# design.net
KiCad netlist of a schematic drawn in Altium Designer
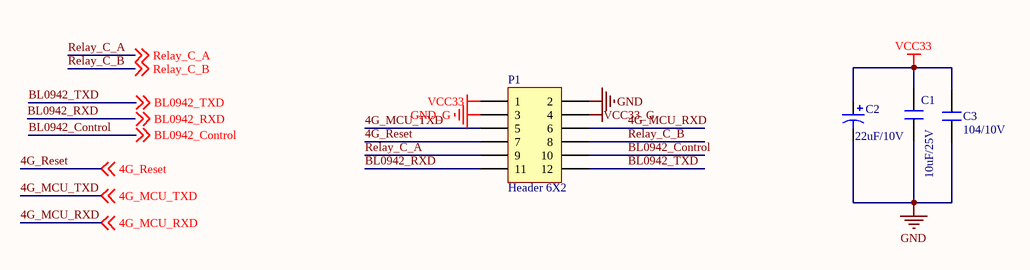
[diagram p0: 连接.SchDoc]

(export (version "E")
  (design (tool "Eeschema 10.0.6"))
  (components
    (comp (ref "C1") (value "10uF/25V") (footprint "0603R") (libsource (lib "ES_Schematic") (part "CAP")))
    (comp (ref "C2")
      (value "22uF/10V")
      (footprint "0805R")
      (description "Polarized Capacitor (Radial)")
      (fields (field (name "PUBLISHER") "Altium Limited"))
      (libsource (lib "Miscellaneous Devices") (part "Cap Pol1"))
    )
    (comp (ref "C3") (value "104/10V") (footprint "0603R") (libsource (lib "ES_Schematic") (part "CAP_1")))
    (comp (ref "P1")
      (value "Header 6X2")
      (footprint "HDR2X6")
      (description "Header, 6-Pin, Dual row")
      (fields (field (name "PUBLISHER") "Altium Limited"))
      (libsource (lib "Miscellaneous Connectors") (part "Header 6X2"))
    )
  )
  (nets
    (net (code "1") (name "4G_MCU_RXD") (class "Default")
      (node (ref "P1") (pin "6") (pinfunction "6_6") (pintype "passive"))
    )
    (net (code "2") (name "4G_MCU_TXD") (class "Default")
      (node (ref "P1") (pin "5") (pinfunction "5_5") (pintype "passive"))
    )
    (net (code "3") (name "4G_Reset") (class "Default")
      (node (ref "P1") (pin "7") (pinfunction "7_7") (pintype "passive"))
    )
    (net (code "4") (name "BL0942_Control") (class "Default")
      (node (ref "P1") (pin "10") (pinfunction "10_10") (pintype "passive"))
    )
    (net (code "5") (name "BL0942_RXD") (class "Default")
      (node (ref "P1") (pin "11") (pinfunction "11_11") (pintype "passive"))
    )
    (net (code "6") (name "BL0942_TXD") (class "Default")
      (node (ref "P1") (pin "12") (pinfunction "12_12") (pintype "passive"))
    )
    (net (code "7") (name "GND") (class "Default")
      (node (ref "C1") (pin "1") (pinfunction "1_1") (pintype "passive"))
      (node (ref "C2") (pin "2") (pinfunction "2_2") (pintype "passive"))
      (node (ref "C3") (pin "1") (pinfunction "1_1") (pintype "passive"))
      (node (ref "P1") (pin "2") (pinfunction "2_2") (pintype "passive"))
    )
    (net (code "8") (name "GND_G") (class "Default")
      (node (ref "P1") (pin "3") (pinfunction "3_3") (pintype "passive"))
    )
    (net (code "9") (name "Relay_C_A") (class "Default")
      (node (ref "P1") (pin "9") (pinfunction "9_9") (pintype "passive"))
    )
    (net (code "10") (name "Relay_C_B") (class "Default")
      (node (ref "P1") (pin "8") (pinfunction "8_8") (pintype "passive"))
    )
    (net (code "11") (name "VCC33") (class "Default")
      (node (ref "C1") (pin "2") (pinfunction "2_2") (pintype "passive"))
      (node (ref "C2") (pin "1") (pinfunction "1_1") (pintype "passive"))
      (node (ref "C3") (pin "2") (pinfunction "2_2") (pintype "passive"))
      (node (ref "P1") (pin "1") (pinfunction "1_1") (pintype "passive"))
    )
    (net (code "12") (name "VCC33_G") (class "Default")
      (node (ref "P1") (pin "4") (pinfunction "4_4") (pintype "passive"))
    )
  )
)
